# Sheet1.net
KiCad netlist of a schematic drawn in Altium Designer
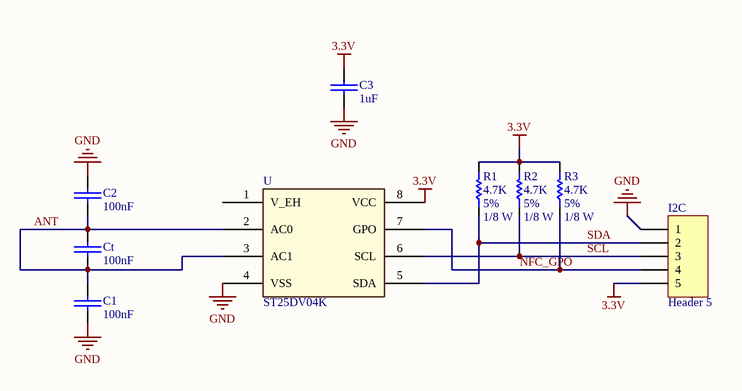
[diagram p0: Sheet1.SchDoc]

(export (version "E")
  (design (tool "Eeschema 10.0.6"))
  (components
    (comp (ref "C1")
      (value "100nF")
      (footprint "SMD_CAP_0805")
      (description "Bipolar Capacitor")
      (fields (field (name "VOLTAGE") "100V") (field (name "DESIGNER") "Saeid Jorablo"))
      (libsource (lib "My_Library") (part "Cap-Bipolar"))
    )
    (comp (ref "C2")
      (value "100nF")
      (footprint "SMD_CAP_0805")
      (description "Bipolar Capacitor")
      (fields (field (name "VOLTAGE") "100V") (field (name "DESIGNER") "Saeid Jorablo"))
      (libsource (lib "My_Library") (part "Cap-Bipolar"))
    )
    (comp (ref "C3")
      (value "1uF")
      (footprint "SMD_CAP_0805")
      (description "Bipolar Capacitor")
      (fields (field (name "VOLTAGE") "100V") (field (name "DESIGNER") "Saeid Jorablo"))
      (libsource (lib "My_Library") (part "Cap-Bipolar"))
    )
    (comp (ref "Ct")
      (value "100nF")
      (footprint "SMD_CAP_0805")
      (description "Bipolar Capacitor")
      (fields (field (name "VOLTAGE") "100V") (field (name "DESIGNER") "Saeid Jorablo"))
      (libsource (lib "My_Library") (part "Cap-Bipolar"))
    )
    (comp (ref "I2C")
      (value "Header 5")
      (footprint "HDR1X5")
      (description "Header, 5-Pin")
      (fields (field (name "PUBLISHER") "Altium Limited"))
      (libsource (lib "Miscellaneous Connectors") (part "Header 5"))
    )
    (comp (ref "R1")
      (value "4.7K")
      (footprint "RES 0805 (2012X06L)")
      (description "Resistor")
      (fields (field (name "TOLERANCE") "5%") (field (name "POWER") "1/8 W"))
      (libsource (lib "My_Library") (part "Resistor"))
    )
    (comp (ref "R2")
      (value "4.7K")
      (footprint "RES 0805 (2012X06L)")
      (description "Resistor")
      (fields (field (name "TOLERANCE") "5%") (field (name "POWER") "1/8 W"))
      (libsource (lib "My_Library") (part "Resistor"))
    )
    (comp (ref "R3")
      (value "4.7K")
      (footprint "RES 0805 (2012X06L)")
      (description "Resistor")
      (fields (field (name "TOLERANCE") "5%") (field (name "POWER") "1/8 W"))
      (libsource (lib "My_Library") (part "Resistor"))
    )
    (comp (ref "U")
      (value "ST25DV04K")
      (footprint "PCBComponent_1")
      (libsource (lib "ST25DV04K") (part "ST25DV04K"))
    )
  )
  (nets
    (net (code "1") (name "/ANT") (class "Default")
      (node (ref "C1") (pin "1") (pinfunction "+_1") (pintype "passive"))
      (node (ref "C2") (pin "2") (pinfunction "-_2") (pintype "passive"))
      (node (ref "Ct") (pin "1") (pinfunction "+_1") (pintype "passive"))
      (node (ref "Ct") (pin "2") (pinfunction "-_2") (pintype "passive"))
      (node (ref "U") (pin "2") (pinfunction "AC0_2") (pintype "passive"))
      (node (ref "U") (pin "3") (pinfunction "AC1_3") (pintype "passive"))
    )
    (net (code "2") (name "/NFC_GPO") (class "Default")
      (node (ref "I2C") (pin "4") (pinfunction "4_4") (pintype "passive"))
      (node (ref "R3") (pin "1") (pinfunction "1_1") (pintype "passive"))
      (node (ref "U") (pin "7") (pinfunction "GPO_7") (pintype "passive"))
    )
    (net (code "3") (name "/SCL") (class "Default")
      (node (ref "I2C") (pin "3") (pinfunction "3_3") (pintype "passive"))
      (node (ref "R2") (pin "1") (pinfunction "1_1") (pintype "passive"))
      (node (ref "U") (pin "6") (pinfunction "SCL_6") (pintype "passive"))
    )
    (net (code "4") (name "/SDA") (class "Default")
      (node (ref "I2C") (pin "2") (pinfunction "2_2") (pintype "passive"))
      (node (ref "R1") (pin "1") (pinfunction "1_1") (pintype "passive"))
      (node (ref "U") (pin "5") (pinfunction "SDA_5") (pintype "passive"))
    )
    (net (code "5") (name "3.3V") (class "Default")
      (node (ref "C3") (pin "1") (pinfunction "+_1") (pintype "passive"))
      (node (ref "I2C") (pin "5") (pinfunction "5_5") (pintype "passive"))
      (node (ref "R1") (pin "2") (pinfunction "2_2") (pintype "passive"))
      (node (ref "R2") (pin "2") (pinfunction "2_2") (pintype "passive"))
      (node (ref "R3") (pin "2") (pinfunction "2_2") (pintype "passive"))
      (node (ref "U") (pin "8") (pinfunction "VCC_8") (pintype "passive"))
    )
    (net (code "6") (name "GND") (class "Default")
      (node (ref "C1") (pin "2") (pinfunction "-_2") (pintype "passive"))
      (node (ref "C2") (pin "1") (pinfunction "+_1") (pintype "passive"))
      (node (ref "C3") (pin "2") (pinfunction "-_2") (pintype "passive"))
      (node (ref "I2C") (pin "1") (pinfunction "1_1") (pintype "passive"))
      (node (ref "U") (pin "4") (pinfunction "VSS_4") (pintype "passive"))
    )
    (net (code "7") (name "unconnected-(U-V_EH-Pad1)") (class "Default")
      (node (ref "U") (pin "1") (pinfunction "V_EH_1") (pintype "passive"))
    )
  )
)
